# Buck_converter_ADJ.net
KiCad netlist of a schematic drawn in Altium Designer
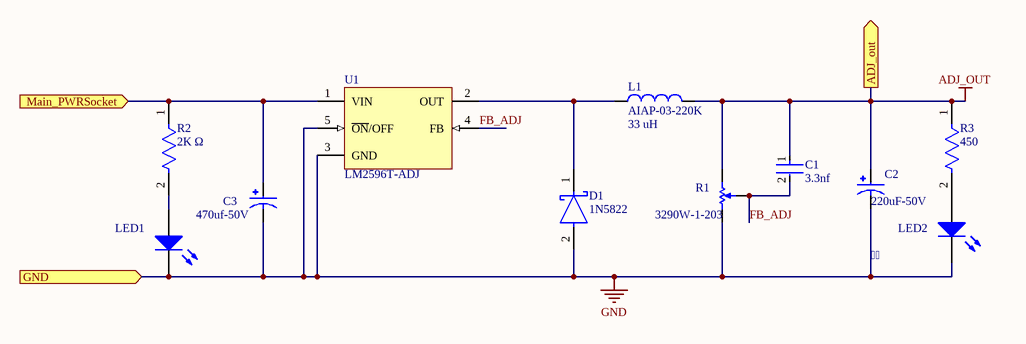
[diagram p0: Buck converter_ADJ.SchDoc]

(export (version "E")
  (design (tool "Eeschema 10.0.6"))
  (components
    (comp (ref "C1")
      (value "3.3nf")
      (footprint "FP-RCE0K1-MFG")
      (description "Cap Ceramic 15pF 50V C0G ±5% Radial 5mm +125°C Automotive Bulk")
      (fields (field (name "TOLERANCE") "5%"))
      (libsource (lib "Altium Content Vault") (part "b4654b650e69147ec39a6b967a45e02"))
    )
    (comp (ref "C2")
      (value "220uF-50V")
      (footprint "EEUFM1H221:CAPPRD500W60D1000H1600")
      (description "FM-A")
      (fields (field (name "MF") "{'manufacturer': u'Panasonic'}") (field (name "MP") "EEUFM1H221"))
      (libsource (lib "*") (part "EEUFM1H221"))
    )
    (comp (ref "C3")
      (value "470uf-50V")
      (footprint "EEUFM1H471:CAPPRD500W60D1250H2000")
      (description "FM-A")
      (fields (field (name "MF") "{'manufacturer': u'Panasonic'}") (field (name "MP") "EEUFM1H471"))
      (libsource (lib "*") (part "EEUFM1H471"))
    )
    (comp (ref "D1")
      (value "1N5822")
      (footprint "FP-DO-201AD-MFG")
      (description "DIODE SCHOTTKY 40V 3A DO201AD")
      (fields
        (field (name "OCTOPART") "https://octopart.com/1n5822-stmicroelectronics-323225")
        (field (name "MANUFACTURER") "STMicroelectronics")
      )
      (libsource (lib "Altium Content Vault") (part "1d6ec82d83fb6aee721767c19dac4b9"))
    )
    (comp (ref "L1")
      (value "AIAP-03-220K")
      (footprint "ABRA-AIAP-02-2_V2")
      (fields
        (field (name "PARTNUMBER") "AIAP-02-102K")
        (field (name "INDUCTANCE") "33 uH")
        (field (name "TOLERANCE") "+/- 10%")
        (field (name "MANUFACTURER") "Abracon")
      )
      (libsource (lib "Altium Content Vault") (part "ABRA-IND-2"))
    )
    (comp (ref "LED1")
      (value "~")
      (footprint "Type 5mm")
      (description "THT LED round mono-color color lens, WL-TMRW, Bright Green")
      (fields (field (name "PARTNUMBER") "151051VS04000") (field (name "MANUFACTURER") "Wuerth Elektronik"))
      (libsource (lib "Altium Content Vault") (part "WE-LED_K1A2-2"))
    )
    (comp (ref "LED2")
      (value "")
      (footprint "Type 5mm")
      (description "THT LED round mono-color color lens, WL-TMRW, Bright Green")
      (fields (field (name "PARTNUMBER") "151051VS04000") (field (name "MANUFACTURER") "Wuerth Elektronik"))
      (libsource (lib "Altium Content Vault") (part "WE-LED_K1A2-2"))
    )
    (comp (ref "R1")
      (value "3290W-1-203")
      (footprint "BOUR-3290W")
      (description "Trimming Potentiometer, 20 KOhm, 1 W, -65 to 150 degC, 3-Pin THD, RoHS, Tube")
      (fields (field (name "MANUFACTURER") "Bourns"))
      (libsource (lib "Altium Content Vault") (part "RES-ADJ-3_A"))
    )
    (comp (ref "R2")
      (value "2K Ω")
      (footprint "FP-MFR-25-MFG")
      (description "RES 1.18K OHM 1/4W 1% AXIAL")
      (fields (field (name "MANUFACTURER") "Yageo") (field (name "TOLERANCE") "1%"))
      (libsource (lib "Altium Content Vault") (part "1029c3af85768c4190bb7ad29bc67b5"))
    )
    (comp (ref "R3")
      (value "450")
      (footprint "FP-MFR-25-MFG")
      (description "RES 1.18K OHM 1/4W 1% AXIAL")
      (fields (field (name "MANUFACTURER") "Yageo") (field (name "TOLERANCE") "1%"))
      (libsource (lib "Altium Content Vault") (part "1029c3af85768c4190bb7ad29bc67b5"))
    )
    (comp (ref "U1")
      (value "LM2596T-ADJ")
      (footprint "NDH0005A")
      (description "SIMPLE SWITCHER® Power Converter 150 KHz 3A Step-Down Voltage Regulator, 5-pin TO-220")
      (fields (field (name "MANUFACTURER") "Texas Instruments"))
      (libsource (lib "Altium Content Vault") (part "PM-REG-LM2575HVT-12"))
    )
  )
  (nets
    (net (code "1") (name "/FB_ADJ") (class "Default")
      (node (ref "C1") (pin "2") (pinfunction "2_2") (pintype "passive"))
      (node (ref "R1") (pin "2") (pinfunction "2_2") (pintype "passive"))
      (node (ref "U1") (pin "4") (pinfunction "FB_4") (pintype "input"))
    )
    (net (code "2") (name "/Main_PWRSocket") (class "Default")
      (node (ref "C3") (pin "P") (pinfunction "P_P") (pintype "passive"))
      (node (ref "R2") (pin "1") (pinfunction "1_1") (pintype "passive"))
      (node (ref "U1") (pin "1") (pinfunction "VIN_1") (pintype "power_in"))
    )
    (net (code "3") (name "ADJ_OUT") (class "Default")
      (node (ref "C1") (pin "1") (pinfunction "1_1") (pintype "passive"))
      (node (ref "C2") (pin "P") (pinfunction "P_P") (pintype "passive"))
      (node (ref "L1") (pin "2") (pinfunction "2_2") (pintype "passive"))
      (node (ref "R1") (pin "3") (pinfunction "3_3") (pintype "passive"))
      (node (ref "R3") (pin "1") (pinfunction "1_1") (pintype "passive"))
    )
    (net (code "4") (name "GND") (class "Default")
      (node (ref "C2") (pin "N") (pinfunction "N_N") (pintype "passive"))
      (node (ref "C3") (pin "N") (pinfunction "N_N") (pintype "passive"))
      (node (ref "D1") (pin "2") (pinfunction "A_2") (pintype "passive"))
      (node (ref "LED1") (pin "1") (pinfunction "K_1") (pintype "passive"))
      (node (ref "LED2") (pin "1") (pinfunction "K_1") (pintype "passive"))
      (node (ref "R1") (pin "1") (pinfunction "1_1") (pintype "passive"))
      (node (ref "U1") (pin "3") (pinfunction "GND_3") (pintype "power_in"))
      (node (ref "U1") (pin "5") (pinfunction "~{ON}/OFF_5") (pintype "input"))
    )
    (net (code "5") (name "Net-(D1-C)") (class "Default")
      (node (ref "D1") (pin "1") (pinfunction "C_1") (pintype "passive"))
      (node (ref "L1") (pin "1") (pinfunction "1_1") (pintype "passive"))
      (node (ref "U1") (pin "2") (pinfunction "OUT_2") (pintype "power_in"))
    )
    (net (code "6") (name "Net-(LED1-A)") (class "Default")
      (node (ref "LED1") (pin "2") (pinfunction "A_2") (pintype "passive"))
      (node (ref "R2") (pin "2") (pinfunction "2_2") (pintype "passive"))
    )
    (net (code "7") (name "Net-(LED2-A)") (class "Default")
      (node (ref "LED2") (pin "2") (pinfunction "A_2") (pintype "passive"))
      (node (ref "R3") (pin "2") (pinfunction "2_2") (pintype "passive"))
    )
  )
)
